# HEADER.net
KiCad netlist of a schematic drawn in Altium Designer
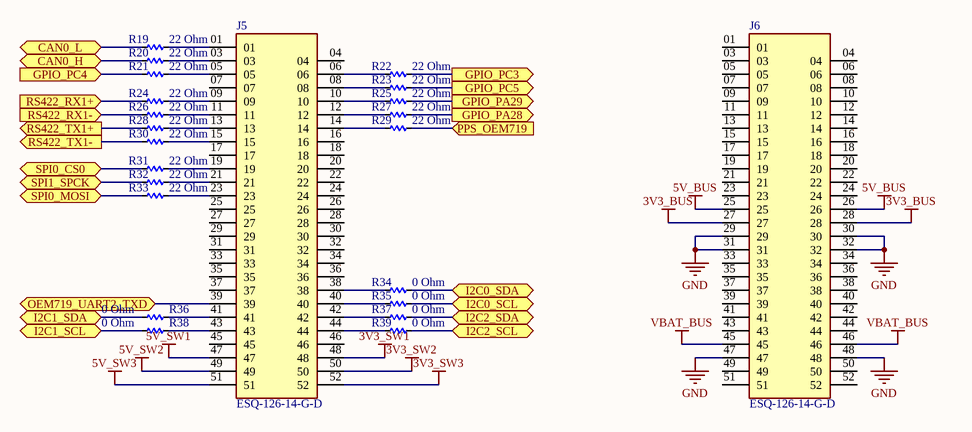
[diagram p0: HEADER.SchDoc]

(export (version "E")
  (design (tool "Eeschema 10.0.6"))
  (components
    (comp (ref "J5")
      (value "ESQ-126-14-G-D")
      (footprint "ESQ-126-14-G-D")
      (description "PC / 104 Connectors Elevated Socket Strip")
      (libsource (lib "3_HuyHung") (part "ESQ-126-14-G-D"))
    )
    (comp (ref "J6")
      (value "ESQ-126-14-G-D")
      (footprint "ESQ-126-14-G-D")
      (description "PC / 104 Connectors Elevated Socket Strip")
      (libsource (lib "3_HuyHung") (part "ESQ-126-14-G-D"))
    )
    (comp (ref "R19")
      (value "22 Ohm")
      (footprint "RES_C_1608X60")
      (description "RES")
      (libsource (lib "LABLIB") (part "_RES_B_2"))
    )
    (comp (ref "R20")
      (value "22 Ohm")
      (footprint "RES_C_1608X60")
      (description "RES")
      (libsource (lib "LABLIB") (part "_RES_B_2"))
    )
    (comp (ref "R21")
      (value "22 Ohm")
      (footprint "RES_C_1608X60")
      (description "RES")
      (libsource (lib "LABLIB") (part "_RES_B_2"))
    )
    (comp (ref "R22")
      (value "22 Ohm")
      (footprint "RES_C_1608X60")
      (description "RES")
      (libsource (lib "LABLIB") (part "_RES_B_2"))
    )
    (comp (ref "R23")
      (value "22 Ohm")
      (footprint "RES_C_1608X60")
      (description "RES")
      (libsource (lib "LABLIB") (part "_RES_B_2"))
    )
    (comp (ref "R24")
      (value "22 Ohm")
      (footprint "RES_C_1608X60")
      (description "RES")
      (libsource (lib "LABLIB") (part "_RES_B_2"))
    )
    (comp (ref "R25")
      (value "22 Ohm")
      (footprint "RES_C_1608X60")
      (description "RES")
      (libsource (lib "LABLIB") (part "_RES_B_2"))
    )
    (comp (ref "R26")
      (value "22 Ohm")
      (footprint "RES_C_1608X60")
      (description "RES")
      (libsource (lib "LABLIB") (part "_RES_B_2"))
    )
    (comp (ref "R27")
      (value "22 Ohm")
      (footprint "RES_C_1608X60")
      (description "RES")
      (libsource (lib "LABLIB") (part "_RES_B_2"))
    )
    (comp (ref "R28")
      (value "22 Ohm")
      (footprint "RES_C_1608X60")
      (description "RES")
      (libsource (lib "LABLIB") (part "_RES_B_2"))
    )
    (comp (ref "R29")
      (value "22 Ohm")
      (footprint "RES_C_1608X60")
      (description "RES")
      (libsource (lib "LABLIB") (part "_RES_B_2"))
    )
    (comp (ref "R30")
      (value "22 Ohm")
      (footprint "RES_C_1608X60")
      (description "RES")
      (libsource (lib "LABLIB") (part "_RES_B_2"))
    )
    (comp (ref "R31")
      (value "22 Ohm")
      (footprint "RES_C_1608X60")
      (description "RES")
      (libsource (lib "LABLIB") (part "_RES_B_2"))
    )
    (comp (ref "R32")
      (value "22 Ohm")
      (footprint "RES_C_1608X60")
      (description "RES")
      (libsource (lib "LABLIB") (part "_RES_B_2"))
    )
    (comp (ref "R33")
      (value "22 Ohm")
      (footprint "RES_C_1608X60")
      (description "RES")
      (libsource (lib "LABLIB") (part "_RES_B_2"))
    )
    (comp (ref "R34")
      (value "0 Ohm")
      (footprint "RES_C_1608X60")
      (description "RES")
      (libsource (lib "LABLIB") (part "_RES_B_2"))
    )
    (comp (ref "R35")
      (value "0 Ohm")
      (footprint "RES_C_1608X60")
      (description "RES")
      (libsource (lib "LABLIB") (part "_RES_B_2"))
    )
    (comp (ref "R36")
      (value "0 Ohm")
      (footprint "RES_C_1608X60")
      (description "RES")
      (libsource (lib "LABLIB") (part "_RES_B_2"))
    )
    (comp (ref "R37")
      (value "0 Ohm")
      (footprint "RES_C_1608X60")
      (description "RES")
      (libsource (lib "LABLIB") (part "_RES_B_2"))
    )
    (comp (ref "R38")
      (value "0 Ohm")
      (footprint "RES_C_1608X60")
      (description "RES")
      (libsource (lib "LABLIB") (part "_RES_B_2"))
    )
    (comp (ref "R39")
      (value "0 Ohm")
      (footprint "RES_C_1608X60")
      (description "RES")
      (libsource (lib "LABLIB") (part "_RES_B_2"))
    )
  )
  (nets
    (net (code "1") (name "/CAN0_H") (class "Default")
      (node (ref "R20") (pin "1") (pinfunction "1_1") (pintype "passive"))
    )
    (net (code "2") (name "/CAN0_L") (class "Default")
      (node (ref "R19") (pin "1") (pinfunction "1_1") (pintype "passive"))
    )
    (net (code "3") (name "/GPIO_PA28") (class "Default")
      (node (ref "R27") (pin "2") (pinfunction "2_2") (pintype "passive"))
    )
    (net (code "4") (name "/GPIO_PA29") (class "Default")
      (node (ref "R25") (pin "2") (pinfunction "2_2") (pintype "passive"))
    )
    (net (code "5") (name "/GPIO_PC3") (class "Default")
      (node (ref "R22") (pin "2") (pinfunction "2_2") (pintype "passive"))
    )
    (net (code "6") (name "/GPIO_PC4") (class "Default")
      (node (ref "R21") (pin "1") (pinfunction "1_1") (pintype "passive"))
    )
    (net (code "7") (name "/GPIO_PC5") (class "Default")
      (node (ref "R23") (pin "2") (pinfunction "2_2") (pintype "passive"))
    )
    (net (code "8") (name "/I2C0_SCL") (class "Default")
      (node (ref "R35") (pin "2") (pinfunction "2_2") (pintype "passive"))
    )
    (net (code "9") (name "/I2C0_SDA") (class "Default")
      (node (ref "R34") (pin "2") (pinfunction "2_2") (pintype "passive"))
    )
    (net (code "10") (name "/I2C1_SCL") (class "Default")
      (node (ref "R38") (pin "1") (pinfunction "1_1") (pintype "passive"))
    )
    (net (code "11") (name "/I2C1_SDA") (class "Default")
      (node (ref "R36") (pin "1") (pinfunction "1_1") (pintype "passive"))
    )
    (net (code "12") (name "/I2C2_SCL") (class "Default")
      (node (ref "R39") (pin "2") (pinfunction "2_2") (pintype "passive"))
    )
    (net (code "13") (name "/I2C2_SDA") (class "Default")
      (node (ref "R37") (pin "2") (pinfunction "2_2") (pintype "passive"))
    )
    (net (code "14") (name "/OEM719_UART2_TXD") (class "Default")
      (node (ref "J5") (pin "39") (pinfunction "39_39") (pintype "passive"))
    )
    (net (code "15") (name "/PPS_OEM719") (class "Default")
      (node (ref "R29") (pin "2") (pinfunction "2_2") (pintype "passive"))
    )
    (net (code "16") (name "/RS422_RX1+") (class "Default")
      (node (ref "R24") (pin "1") (pinfunction "1_1") (pintype "passive"))
    )
    (net (code "17") (name "/RS422_RX1-") (class "Default")
      (node (ref "R26") (pin "1") (pinfunction "1_1") (pintype "passive"))
    )
    (net (code "18") (name "/RS422_TX1+") (class "Default")
      (node (ref "R28") (pin "1") (pinfunction "1_1") (pintype "passive"))
    )
    (net (code "19") (name "/RS422_TX1-") (class "Default")
      (node (ref "R30") (pin "1") (pinfunction "1_1") (pintype "passive"))
    )
    (net (code "20") (name "/SPI0_CS0") (class "Default")
      (node (ref "R31") (pin "1") (pinfunction "1_1") (pintype "passive"))
    )
    (net (code "21") (name "/SPI0_MOSI") (class "Default")
      (node (ref "R33") (pin "1") (pinfunction "1_1") (pintype "passive"))
    )
    (net (code "22") (name "/SPI1_SPCK") (class "Default")
      (node (ref "R32") (pin "1") (pinfunction "1_1") (pintype "passive"))
    )
    (net (code "23") (name "3V3_BUS") (class "Default")
      (node (ref "J6") (pin "27") (pinfunction "27_27") (pintype "passive"))
      (node (ref "J6") (pin "28") (pinfunction "28_28") (pintype "passive"))
    )
    (net (code "24") (name "3V3_SW1") (class "Default")
      (node (ref "J5") (pin "48") (pinfunction "48_48") (pintype "passive"))
    )
    (net (code "25") (name "3V3_SW2") (class "Default")
      (node (ref "J5") (pin "50") (pinfunction "50_50") (pintype "passive"))
    )
    (net (code "26") (name "3V3_SW3") (class "Default")
      (node (ref "J5") (pin "52") (pinfunction "52_52") (pintype "passive"))
    )
    (net (code "27") (name "5V_BUS") (class "Default")
      (node (ref "J6") (pin "25") (pinfunction "25_25") (pintype "passive"))
      (node (ref "J6") (pin "26") (pinfunction "26_26") (pintype "passive"))
    )
    (net (code "28") (name "5V_SW1") (class "Default")
      (node (ref "J5") (pin "47") (pinfunction "47_47") (pintype "passive"))
    )
    (net (code "29") (name "5V_SW2") (class "Default")
      (node (ref "J5") (pin "49") (pinfunction "49_49") (pintype "passive"))
    )
    (net (code "30") (name "5V_SW3") (class "Default")
      (node (ref "J5") (pin "51") (pinfunction "51_51") (pintype "passive"))
    )
    (net (code "31") (name "GND") (class "Default")
      (node (ref "J6") (pin "29") (pinfunction "29_29") (pintype "passive"))
      (node (ref "J6") (pin "30") (pinfunction "30_30") (pintype "passive"))
      (node (ref "J6") (pin "31") (pinfunction "31_31") (pintype "passive"))
      (node (ref "J6") (pin "32") (pinfunction "32_32") (pintype "passive"))
      (node (ref "J6") (pin "47") (pinfunction "47_47") (pintype "passive"))
      (node (ref "J6") (pin "48") (pinfunction "48_48") (pintype "passive"))
    )
    (net (code "32") (name "Net-(J5-Pad01)") (class "Default")
      (node (ref "J5") (pin "01") (pinfunction "01_01") (pintype "passive"))
      (node (ref "R19") (pin "2") (pinfunction "2_2") (pintype "passive"))
    )
    (net (code "33") (name "Net-(J5-Pad03)") (class "Default")
      (node (ref "J5") (pin "03") (pinfunction "03_03") (pintype "passive"))
      (node (ref "R20") (pin "2") (pinfunction "2_2") (pintype "passive"))
    )
    (net (code "34") (name "Net-(J5-Pad05)") (class "Default")
      (node (ref "J5") (pin "05") (pinfunction "05_05") (pintype "passive"))
      (node (ref "R21") (pin "2") (pinfunction "2_2") (pintype "passive"))
    )
    (net (code "35") (name "Net-(J5-Pad06)") (class "Default")
      (node (ref "J5") (pin "06") (pinfunction "06_06") (pintype "passive"))
      (node (ref "R22") (pin "1") (pinfunction "1_1") (pintype "passive"))
    )
    (net (code "36") (name "Net-(J5-Pad08)") (class "Default")
      (node (ref "J5") (pin "08") (pinfunction "08_08") (pintype "passive"))
      (node (ref "R23") (pin "1") (pinfunction "1_1") (pintype "passive"))
    )
    (net (code "37") (name "Net-(J5-Pad09)") (class "Default")
      (node (ref "J5") (pin "09") (pinfunction "09_09") (pintype "passive"))
      (node (ref "R24") (pin "2") (pinfunction "2_2") (pintype "passive"))
    )
    (net (code "38") (name "Net-(J5-Pad10)") (class "Default")
      (node (ref "J5") (pin "10") (pinfunction "10_10") (pintype "passive"))
      (node (ref "R25") (pin "1") (pinfunction "1_1") (pintype "passive"))
    )
    (net (code "39") (name "Net-(J5-Pad11)") (class "Default")
      (node (ref "J5") (pin "11") (pinfunction "11_11") (pintype "passive"))
      (node (ref "R26") (pin "2") (pinfunction "2_2") (pintype "passive"))
    )
    (net (code "40") (name "Net-(J5-Pad12)") (class "Default")
      (node (ref "J5") (pin "12") (pinfunction "12_12") (pintype "passive"))
      (node (ref "R27") (pin "1") (pinfunction "1_1") (pintype "passive"))
    )
    (net (code "41") (name "Net-(J5-Pad13)") (class "Default")
      (node (ref "J5") (pin "13") (pinfunction "13_13") (pintype "passive"))
      (node (ref "R28") (pin "2") (pinfunction "2_2") (pintype "passive"))
    )
    (net (code "42") (name "Net-(J5-Pad14)") (class "Default")
      (node (ref "J5") (pin "14") (pinfunction "14_14") (pintype "passive"))
      (node (ref "R29") (pin "1") (pinfunction "1_1") (pintype "passive"))
    )
    (net (code "43") (name "Net-(J5-Pad15)") (class "Default")
      (node (ref "J5") (pin "15") (pinfunction "15_15") (pintype "passive"))
      (node (ref "R30") (pin "2") (pinfunction "2_2") (pintype "passive"))
    )
    (net (code "44") (name "Net-(J5-Pad19)") (class "Default")
      (node (ref "J5") (pin "19") (pinfunction "19_19") (pintype "passive"))
      (node (ref "R31") (pin "2") (pinfunction "2_2") (pintype "passive"))
    )
    (net (code "45") (name "Net-(J5-Pad21)") (class "Default")
      (node (ref "J5") (pin "21") (pinfunction "21_21") (pintype "passive"))
      (node (ref "R32") (pin "2") (pinfunction "2_2") (pintype "passive"))
    )
    (net (code "46") (name "Net-(J5-Pad23)") (class "Default")
      (node (ref "J5") (pin "23") (pinfunction "23_23") (pintype "passive"))
      (node (ref "R33") (pin "2") (pinfunction "2_2") (pintype "passive"))
    )
    (net (code "47") (name "Net-(J5-Pad38)") (class "Default")
      (node (ref "J5") (pin "38") (pinfunction "38_38") (pintype "passive"))
      (node (ref "R34") (pin "1") (pinfunction "1_1") (pintype "passive"))
    )
    (net (code "48") (name "Net-(J5-Pad40)") (class "Default")
      (node (ref "J5") (pin "40") (pinfunction "40_40") (pintype "passive"))
      (node (ref "R35") (pin "1") (pinfunction "1_1") (pintype "passive"))
    )
    (net (code "49") (name "Net-(J5-Pad41)") (class "Default")
      (node (ref "J5") (pin "41") (pinfunction "41_41") (pintype "passive"))
      (node (ref "R36") (pin "2") (pinfunction "2_2") (pintype "passive"))
    )
    (net (code "50") (name "Net-(J5-Pad42)") (class "Default")
      (node (ref "J5") (pin "42") (pinfunction "42_42") (pintype "passive"))
      (node (ref "R37") (pin "1") (pinfunction "1_1") (pintype "passive"))
    )
    (net (code "51") (name "Net-(J5-Pad43)") (class "Default")
      (node (ref "J5") (pin "43") (pinfunction "43_43") (pintype "passive"))
      (node (ref "R38") (pin "2") (pinfunction "2_2") (pintype "passive"))
    )
    (net (code "52") (name "Net-(J5-Pad44)") (class "Default")
      (node (ref "J5") (pin "44") (pinfunction "44_44") (pintype "passive"))
      (node (ref "R39") (pin "1") (pinfunction "1_1") (pintype "passive"))
    )
    (net (code "53") (name "VBAT_BUS") (class "Default")
      (node (ref "J6") (pin "45") (pinfunction "45_45") (pintype "passive"))
      (node (ref "J6") (pin "46") (pinfunction "46_46") (pintype "passive"))
    )
    (net (code "54") (name "unconnected-(J5-Pad04)") (class "Default")
      (node (ref "J5") (pin "04") (pinfunction "04_04") (pintype "passive"))
    )
    (net (code "55") (name "unconnected-(J5-Pad07)") (class "Default")
      (node (ref "J5") (pin "07") (pinfunction "07_07") (pintype "passive"))
    )
    (net (code "56") (name "unconnected-(J5-Pad16)") (class "Default")
      (node (ref "J5") (pin "16") (pinfunction "16_16") (pintype "passive"))
    )
    (net (code "57") (name "unconnected-(J5-Pad17)") (class "Default")
      (node (ref "J5") (pin "17") (pinfunction "17_17") (pintype "passive"))
    )
    (net (code "58") (name "unconnected-(J5-Pad18)") (class "Default")
      (node (ref "J5") (pin "18") (pinfunction "18_18") (pintype "passive"))
    )
    (net (code "59") (name "unconnected-(J5-Pad20)") (class "Default")
      (node (ref "J5") (pin "20") (pinfunction "20_20") (pintype "passive"))
    )
    (net (code "60") (name "unconnected-(J5-Pad22)") (class "Default")
      (node (ref "J5") (pin "22") (pinfunction "22_22") (pintype "passive"))
    )
    (net (code "61") (name "unconnected-(J5-Pad24)") (class "Default")
      (node (ref "J5") (pin "24") (pinfunction "24_24") (pintype "passive"))
    )
    (net (code "62") (name "unconnected-(J5-Pad25)") (class "Default")
      (node (ref "J5") (pin "25") (pinfunction "25_25") (pintype "passive"))
    )
    (net (code "63") (name "unconnected-(J5-Pad26)") (class "Default")
      (node (ref "J5") (pin "26") (pinfunction "26_26") (pintype "passive"))
    )
    (net (code "64") (name "unconnected-(J5-Pad27)") (class "Default")
      (node (ref "J5") (pin "27") (pinfunction "27_27") (pintype "passive"))
    )
    (net (code "65") (name "unconnected-(J5-Pad28)") (class "Default")
      (node (ref "J5") (pin "28") (pinfunction "28_28") (pintype "passive"))
    )
    (net (code "66") (name "unconnected-(J5-Pad29)") (class "Default")
      (node (ref "J5") (pin "29") (pinfunction "29_29") (pintype "passive"))
    )
    (net (code "67") (name "unconnected-(J5-Pad30)") (class "Default")
      (node (ref "J5") (pin "30") (pinfunction "30_30") (pintype "passive"))
    )
    (net (code "68") (name "unconnected-(J5-Pad31)") (class "Default")
      (node (ref "J5") (pin "31") (pinfunction "31_31") (pintype "passive"))
    )
    (net (code "69") (name "unconnected-(J5-Pad32)") (class "Default")
      (node (ref "J5") (pin "32") (pinfunction "32_32") (pintype "passive"))
    )
    (net (code "70") (name "unconnected-(J5-Pad33)") (class "Default")
      (node (ref "J5") (pin "33") (pinfunction "33_33") (pintype "passive"))
    )
    (net (code "71") (name "unconnected-(J5-Pad34)") (class "Default")
      (node (ref "J5") (pin "34") (pinfunction "34_34") (pintype "passive"))
    )
    (net (code "72") (name "unconnected-(J5-Pad35)") (class "Default")
      (node (ref "J5") (pin "35") (pinfunction "35_35") (pintype "passive"))
    )
    (net (code "73") (name "unconnected-(J5-Pad36)") (class "Default")
      (node (ref "J5") (pin "36") (pinfunction "36_36") (pintype "passive"))
    )
    (net (code "74") (name "unconnected-(J5-Pad37)") (class "Default")
      (node (ref "J5") (pin "37") (pinfunction "37_37") (pintype "passive"))
    )
    (net (code "75") (name "unconnected-(J5-Pad45)") (class "Default")
      (node (ref "J5") (pin "45") (pinfunction "45_45") (pintype "passive"))
    )
    (net (code "76") (name "unconnected-(J5-Pad46)") (class "Default")
      (node (ref "J5") (pin "46") (pinfunction "46_46") (pintype "passive"))
    )
    (net (code "77") (name "unconnected-(J6-Pad01)") (class "Default")
      (node (ref "J6") (pin "01") (pinfunction "01_01") (pintype "passive"))
    )
    (net (code "78") (name "unconnected-(J6-Pad03)") (class "Default")
      (node (ref "J6") (pin "03") (pinfunction "03_03") (pintype "passive"))
    )
    (net (code "79") (name "unconnected-(J6-Pad04)") (class "Default")
      (node (ref "J6") (pin "04") (pinfunction "04_04") (pintype "passive"))
    )
    (net (code "80") (name "unconnected-(J6-Pad05)") (class "Default")
      (node (ref "J6") (pin "05") (pinfunction "05_05") (pintype "passive"))
    )
    (net (code "81") (name "unconnected-(J6-Pad06)") (class "Default")
      (node (ref "J6") (pin "06") (pinfunction "06_06") (pintype "passive"))
    )
    (net (code "82") (name "unconnected-(J6-Pad07)") (class "Default")
      (node (ref "J6") (pin "07") (pinfunction "07_07") (pintype "passive"))
    )
    (net (code "83") (name "unconnected-(J6-Pad08)") (class "Default")
      (node (ref "J6") (pin "08") (pinfunction "08_08") (pintype "passive"))
    )
    (net (code "84") (name "unconnected-(J6-Pad09)") (class "Default")
      (node (ref "J6") (pin "09") (pinfunction "09_09") (pintype "passive"))
    )
    (net (code "85") (name "unconnected-(J6-Pad10)") (class "Default")
      (node (ref "J6") (pin "10") (pinfunction "10_10") (pintype "passive"))
    )
    (net (code "86") (name "unconnected-(J6-Pad11)") (class "Default")
      (node (ref "J6") (pin "11") (pinfunction "11_11") (pintype "passive"))
    )
    (net (code "87") (name "unconnected-(J6-Pad12)") (class "Default")
      (node (ref "J6") (pin "12") (pinfunction "12_12") (pintype "passive"))
    )
    (net (code "88") (name "unconnected-(J6-Pad13)") (class "Default")
      (node (ref "J6") (pin "13") (pinfunction "13_13") (pintype "passive"))
    )
    (net (code "89") (name "unconnected-(J6-Pad14)") (class "Default")
      (node (ref "J6") (pin "14") (pinfunction "14_14") (pintype "passive"))
    )
    (net (code "90") (name "unconnected-(J6-Pad15)") (class "Default")
      (node (ref "J6") (pin "15") (pinfunction "15_15") (pintype "passive"))
    )
    (net (code "91") (name "unconnected-(J6-Pad16)") (class "Default")
      (node (ref "J6") (pin "16") (pinfunction "16_16") (pintype "passive"))
    )
    (net (code "92") (name "unconnected-(J6-Pad17)") (class "Default")
      (node (ref "J6") (pin "17") (pinfunction "17_17") (pintype "passive"))
    )
    (net (code "93") (name "unconnected-(J6-Pad18)") (class "Default")
      (node (ref "J6") (pin "18") (pinfunction "18_18") (pintype "passive"))
    )
    (net (code "94") (name "unconnected-(J6-Pad19)") (class "Default")
      (node (ref "J6") (pin "19") (pinfunction "19_19") (pintype "passive"))
    )
    (net (code "95") (name "unconnected-(J6-Pad20)") (class "Default")
      (node (ref "J6") (pin "20") (pinfunction "20_20") (pintype "passive"))
    )
    (net (code "96") (name "unconnected-(J6-Pad21)") (class "Default")
      (node (ref "J6") (pin "21") (pinfunction "21_21") (pintype "passive"))
    )
    (net (code "97") (name "unconnected-(J6-Pad22)") (class "Default")
      (node (ref "J6") (pin "22") (pinfunction "22_22") (pintype "passive"))
    )
    (net (code "98") (name "unconnected-(J6-Pad23)") (class "Default")
      (node (ref "J6") (pin "23") (pinfunction "23_23") (pintype "passive"))
    )
    (net (code "99") (name "unconnected-(J6-Pad24)") (class "Default")
      (node (ref "J6") (pin "24") (pinfunction "24_24") (pintype "passive"))
    )
    (net (code "100") (name "unconnected-(J6-Pad33)") (class "Default")
      (node (ref "J6") (pin "33") (pinfunction "33_33") (pintype "passive"))
    )
    (net (code "101") (name "unconnected-(J6-Pad34)") (class "Default")
      (node (ref "J6") (pin "34") (pinfunction "34_34") (pintype "passive"))
    )
    (net (code "102") (name "unconnected-(J6-Pad35)") (class "Default")
      (node (ref "J6") (pin "35") (pinfunction "35_35") (pintype "passive"))
    )
    (net (code "103") (name "unconnected-(J6-Pad36)") (class "Default")
      (node (ref "J6") (pin "36") (pinfunction "36_36") (pintype "passive"))
    )
    (net (code "104") (name "unconnected-(J6-Pad37)") (class "Default")
      (node (ref "J6") (pin "37") (pinfunction "37_37") (pintype "passive"))
    )
    (net (code "105") (name "unconnected-(J6-Pad38)") (class "Default")
      (node (ref "J6") (pin "38") (pinfunction "38_38") (pintype "passive"))
    )
    (net (code "106") (name "unconnected-(J6-Pad39)") (class "Default")
      (node (ref "J6") (pin "39") (pinfunction "39_39") (pintype "passive"))
    )
    (net (code "107") (name "unconnected-(J6-Pad40)") (class "Default")
      (node (ref "J6") (pin "40") (pinfunction "40_40") (pintype "passive"))
    )
    (net (code "108") (name "unconnected-(J6-Pad41)") (class "Default")
      (node (ref "J6") (pin "41") (pinfunction "41_41") (pintype "passive"))
    )
    (net (code "109") (name "unconnected-(J6-Pad42)") (class "Default")
      (node (ref "J6") (pin "42") (pinfunction "42_42") (pintype "passive"))
    )
    (net (code "110") (name "unconnected-(J6-Pad43)") (class "Default")
      (node (ref "J6") (pin "43") (pinfunction "43_43") (pintype "passive"))
    )
    (net (code "111") (name "unconnected-(J6-Pad44)") (class "Default")
      (node (ref "J6") (pin "44") (pinfunction "44_44") (pintype "passive"))
    )
    (net (code "112") (name "unconnected-(J6-Pad49)") (class "Default")
      (node (ref "J6") (pin "49") (pinfunction "49_49") (pintype "passive"))
    )
    (net (code "113") (name "unconnected-(J6-Pad50)") (class "Default")
      (node (ref "J6") (pin "50") (pinfunction "50_50") (pintype "passive"))
    )
    (net (code "114") (name "unconnected-(J6-Pad51)") (class "Default")
      (node (ref "J6") (pin "51") (pinfunction "51_51") (pintype "passive"))
    )
    (net (code "115") (name "unconnected-(J6-Pad52)") (class "Default")
      (node (ref "J6") (pin "52") (pinfunction "52_52") (pintype "passive"))
    )
  )
)
